# inductive-conductivity-meter_coil_board.net
KiCad netlist of a schematic drawn in EAGLE
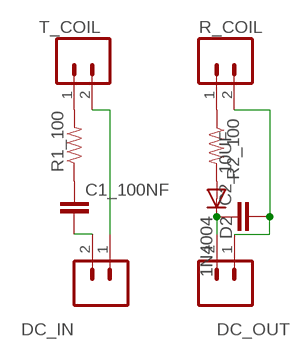
[diagram p0: schematic, sheet 1]

(export (version "E")
  (design (tool "Eeschema 10.0.6"))
  (components
    (comp (ref "C1_100NF")
      (value "CAPPTH1")
      (footprint "eagle-import:CAP-PTH-5MM")
      (libsource (lib "eagle-import") (part "CAPPTH1"))
    )
    (comp (ref "C2_10UF")
      (value "CAPPTH1")
      (footprint "eagle-import:CAP-PTH-5MM")
      (libsource (lib "eagle-import") (part "CAPPTH1"))
    )
    (comp (ref "D2")
      (value "1N4004")
      (footprint "eagle-import:DO41-10")
      (libsource (lib "eagle-import") (part "1N4004"))
    )
    (comp (ref "DC_IN")
      (value "M02PTH")
      (footprint "eagle-import:1X02")
      (libsource (lib "eagle-import") (part "M02PTH"))
    )
    (comp (ref "DC_OUT")
      (value "M02PTH")
      (footprint "eagle-import:1X02")
      (libsource (lib "eagle-import") (part "M02PTH"))
    )
    (comp (ref "R1_100")
      (value "RESISTOREZ")
      (footprint "eagle-import:AXIAL-0.3EZ")
      (libsource (lib "eagle-import") (part "RESISTOREZ"))
    )
    (comp (ref "R2_100")
      (value "RESISTOREZ")
      (footprint "eagle-import:AXIAL-0.3EZ")
      (libsource (lib "eagle-import") (part "RESISTOREZ"))
    )
    (comp (ref "R_COIL")
      (value "M02PTH")
      (footprint "eagle-import:1X02")
      (libsource (lib "eagle-import") (part "M02PTH"))
    )
    (comp (ref "T_COIL")
      (value "M02PTH")
      (footprint "eagle-import:1X02")
      (libsource (lib "eagle-import") (part "M02PTH"))
    )
  )
  (nets
    (net (code "1") (name "Net-(C1_100NF-Pad2)") (class "Default")
      (node (ref "C1_100NF") (pin "2") (pinfunction "2_2") (pintype "passive"))
      (node (ref "DC_IN") (pin "2") (pinfunction "2_2") (pintype "passive"))
    )
    (net (code "2") (name "Net-(C2_10UF-Pad1)") (class "Default")
      (node (ref "C2_10UF") (pin "1") (pinfunction "1_1") (pintype "passive"))
      (node (ref "D2") (pin "C") (pinfunction "C_C") (pintype "passive"))
      (node (ref "DC_OUT") (pin "2") (pinfunction "2_2") (pintype "passive"))
    )
    (net (code "3") (name "Net-(C2_10UF-Pad2)") (class "Default")
      (node (ref "C2_10UF") (pin "2") (pinfunction "2_2") (pintype "passive"))
      (node (ref "DC_OUT") (pin "1") (pinfunction "1_1") (pintype "passive"))
      (node (ref "R_COIL") (pin "2") (pinfunction "2_2") (pintype "passive"))
    )
    (net (code "4") (name "Net-(DC_IN-Pad1)") (class "Default")
      (node (ref "DC_IN") (pin "1") (pinfunction "1_1") (pintype "passive"))
      (node (ref "T_COIL") (pin "2") (pinfunction "2_2") (pintype "passive"))
    )
    (net (code "5") (name "Net-(R1_100-1)") (class "Default")
      (node (ref "C1_100NF") (pin "1") (pinfunction "1_1") (pintype "passive"))
      (node (ref "R1_100") (pin "P$1") (pinfunction "1_P$1") (pintype "passive"))
    )
    (net (code "6") (name "Net-(R1_100-2)") (class "Default")
      (node (ref "R1_100") (pin "P$2") (pinfunction "2_P$2") (pintype "passive"))
      (node (ref "T_COIL") (pin "1") (pinfunction "1_1") (pintype "passive"))
    )
    (net (code "7") (name "Net-(R2_100-1)") (class "Default")
      (node (ref "R2_100") (pin "P$1") (pinfunction "1_P$1") (pintype "passive"))
      (node (ref "R_COIL") (pin "1") (pinfunction "1_1") (pintype "passive"))
    )
    (net (code "8") (name "Net-(R2_100-2)") (class "Default")
      (node (ref "D2") (pin "A") (pinfunction "A_A") (pintype "passive"))
      (node (ref "R2_100") (pin "P$2") (pinfunction "2_P$2") (pintype "passive"))
    )
  )
)
